# MCU025A_XDS110_USB_Power.net
KiCad netlist of a schematic drawn in Altium Designer
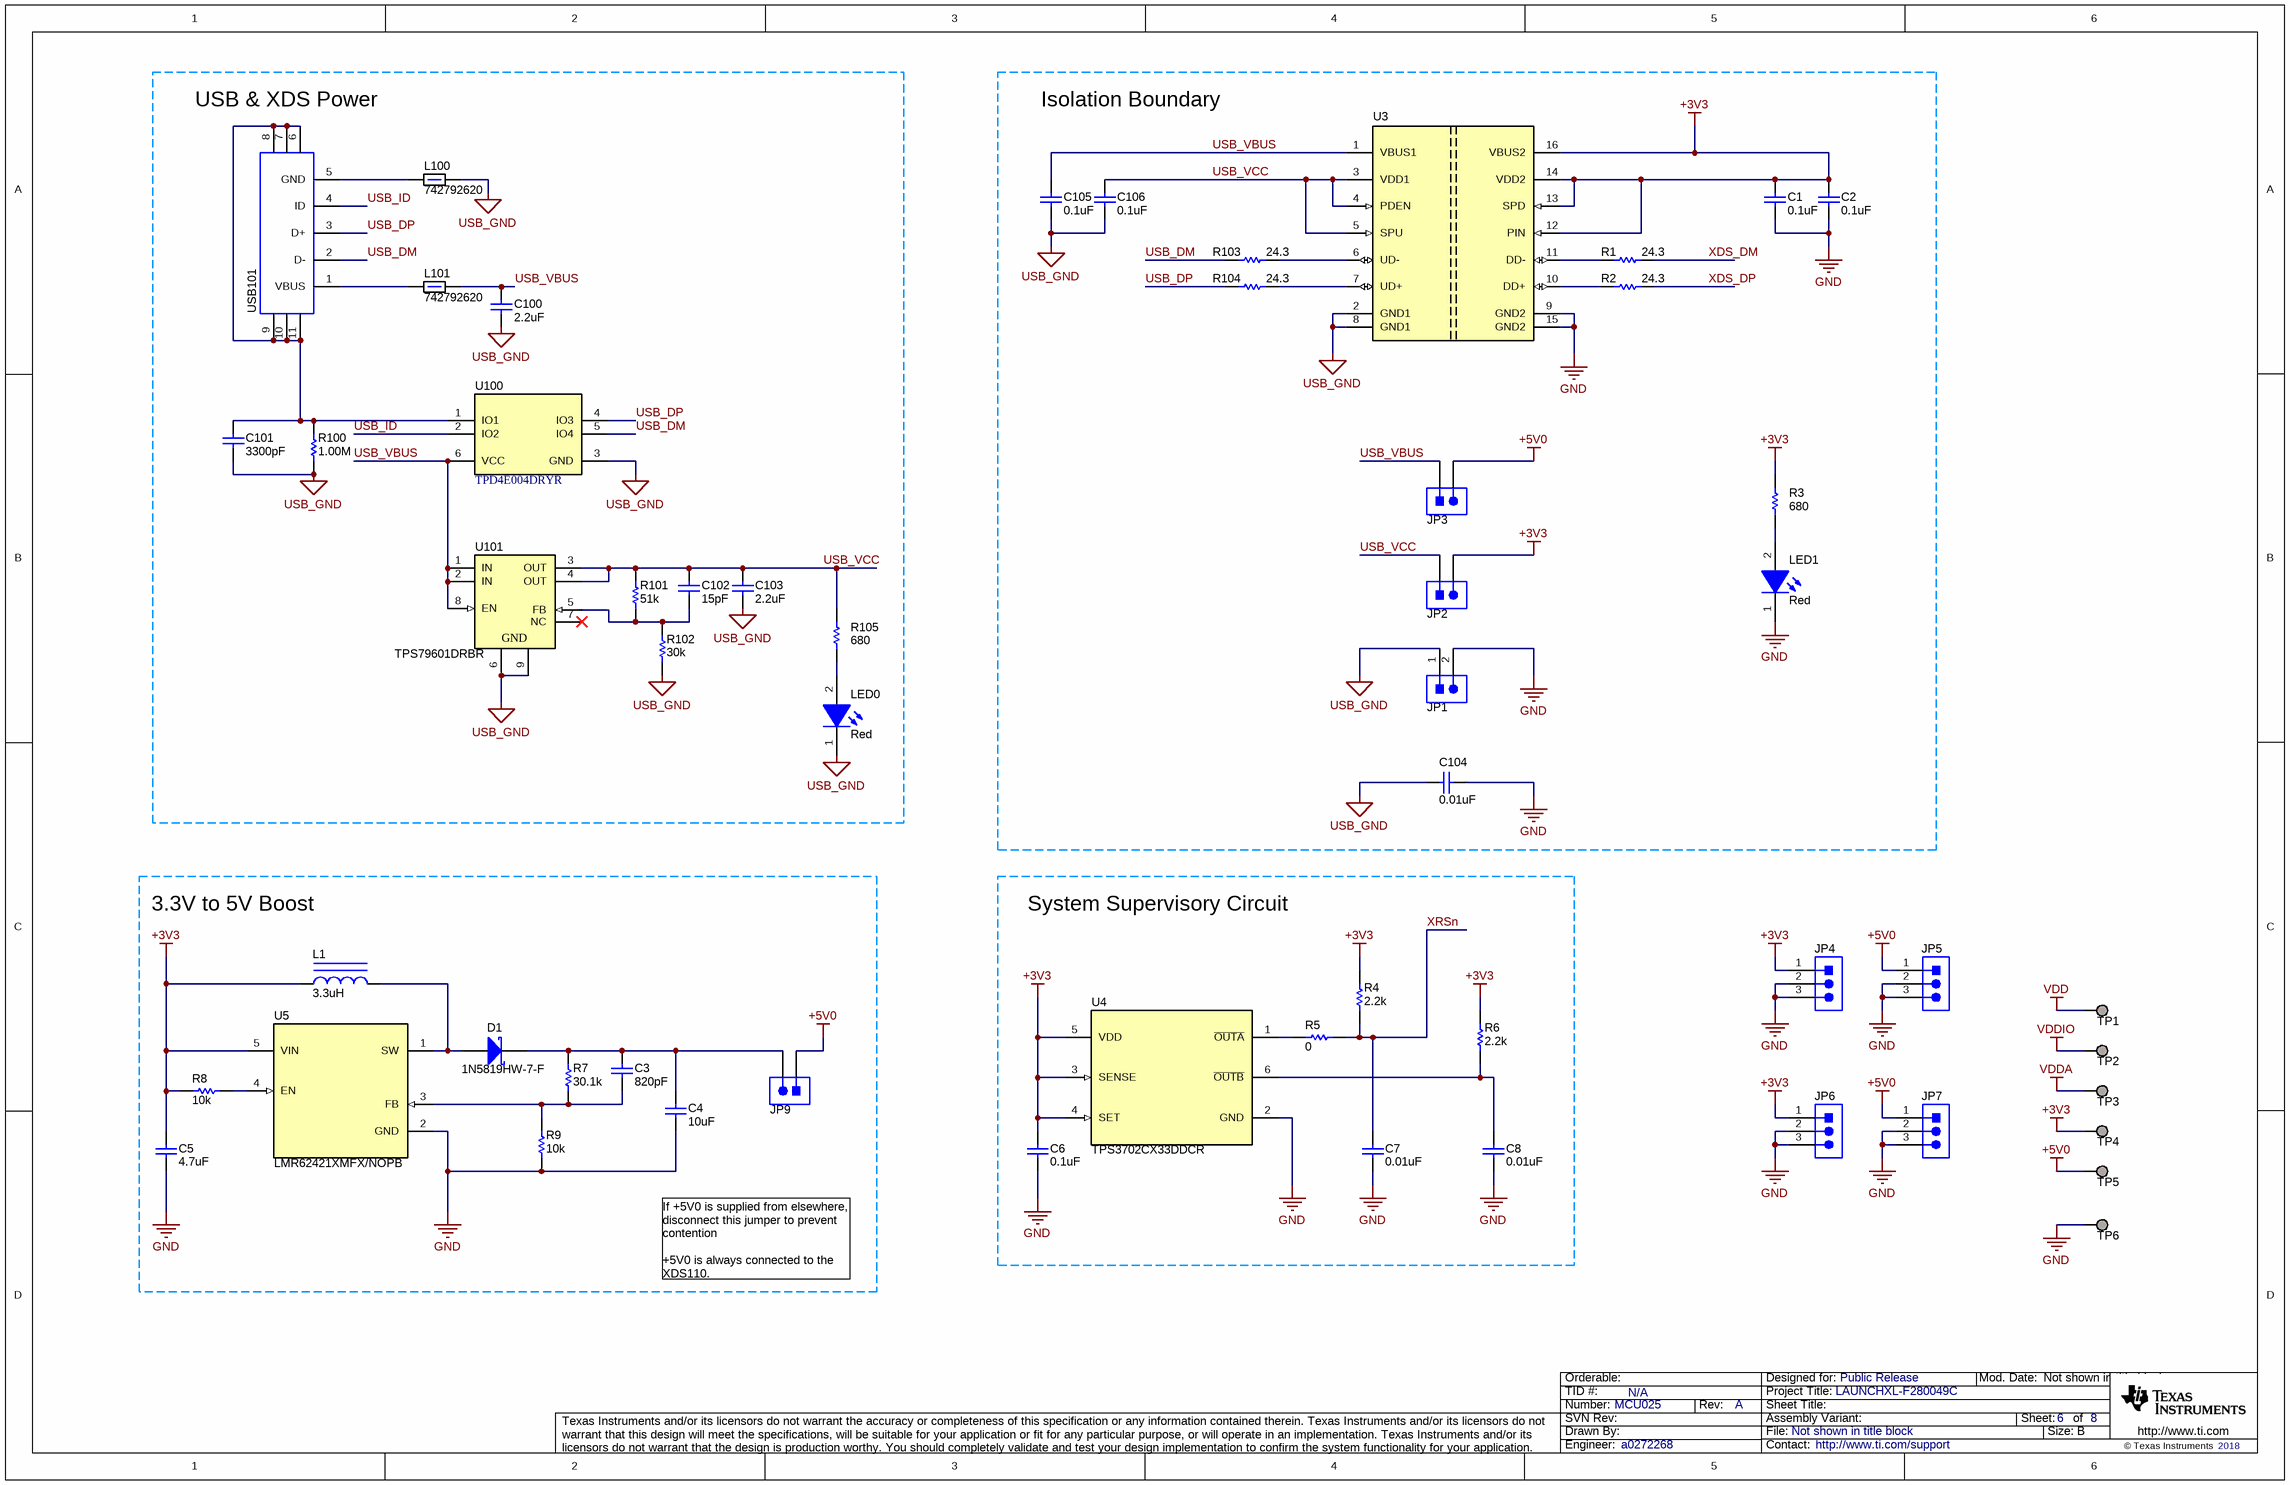
[diagram p0: MCU025A_XDS110_USB_Power.SchDoc]

(export (version "E")
  (design (tool "Eeschema 10.0.6"))
  (components
    (comp (ref "C1")
      (value "GRM155R71A104KA01D")
      (footprint "0402")
      (description "CAP, CERM, 0.1 uF, 10 V, +/- 10%, X7R, 0402")
      (fields
        (field (name "VALUEDISPLAYED") "0.1uF")
        (field (name "MANUFACTURER") "MuRata")
        (field (name "PUBLISHER") "Texas Instruments")
      )
      (libsource (lib "Altium Vault - TI") (part "Capacitor"))
    )
    (comp (ref "C2")
      (value "GRM155R71A104KA01D")
      (footprint "0402")
      (description "CAP, CERM, 0.1 uF, 10 V, +/- 10%, X7R, 0402")
      (fields
        (field (name "VALUEDISPLAYED") "0.1uF")
        (field (name "MANUFACTURER") "MuRata")
        (field (name "PUBLISHER") "Texas Instruments")
      )
      (libsource (lib "Altium Vault - TI") (part "Capacitor"))
    )
    (comp (ref "C3")
      (value "GRM1555C1H821JA01D")
      (footprint "0402")
      (description "CAP, CERM, 820 pF, 50 V, +/- 5%, C0G/NP0, 0402")
      (fields
        (field (name "VALUEDISPLAYED") "820pF")
        (field (name "MANUFACTURER") "MuRata")
        (field (name "PUBLISHER") "Texas Instruments")
      )
      (libsource (lib "Altium Vault - TI") (part "Capacitor"))
    )
    (comp (ref "C4")
      (value "GRM32DR71E106KA12L")
      (footprint "1210_220")
      (description "CAP, CERM, 10 uF, 25 V, +/- 10%, X7R, 1210")
      (fields
        (field (name "VALUEDISPLAYED") "10uF")
        (field (name "MANUFACTURER") "MuRata")
        (field (name "PUBLISHER") "Texas Instruments")
      )
      (libsource (lib "Altium Vault - TI") (part "Capacitor"))
    )
    (comp (ref "C5")
      (value "GRM155R60J475ME47D")
      (footprint "0402")
      (description "CAP, CERM, 4.7 uF, 6.3 V, +/- 20%, X5R, 0402")
      (fields
        (field (name "VALUEDISPLAYED") "4.7uF")
        (field (name "MANUFACTURER") "MuRata")
        (field (name "PUBLISHER") "Texas Instruments")
      )
      (libsource (lib "Altium Vault - TI") (part "Capacitor"))
    )
    (comp (ref "C6")
      (value "GRM155R71A104KA01D")
      (footprint "0402")
      (description "CAP, CERM, 0.1 uF, 10 V, +/- 10%, X7R, 0402")
      (fields
        (field (name "VALUEDISPLAYED") "0.1uF")
        (field (name "MANUFACTURER") "MuRata")
        (field (name "PUBLISHER") "Texas Instruments")
      )
      (libsource (lib "Altium Vault - TI") (part "Capacitor"))
    )
    (comp (ref "C7")
      (value "GRM155R71E103KA01D")
      (footprint "0402")
      (description "CAP, CERM, 0.01 uF, 25 V, +/- 10%, X7R, 0402")
      (fields
        (field (name "VALUEDISPLAYED") "0.01uF")
        (field (name "MANUFACTURER") "MuRata")
        (field (name "PUBLISHER") "Texas Instruments")
      )
      (libsource (lib "Altium Vault - TI") (part "Capacitor"))
    )
    (comp (ref "C8")
      (value "GRM155R71E103KA01D")
      (footprint "0402")
      (description "CAP, CERM, 0.01 uF, 25 V, +/- 10%, X7R, 0402")
      (fields
        (field (name "VALUEDISPLAYED") "0.01uF")
        (field (name "MANUFACTURER") "MuRata")
        (field (name "PUBLISHER") "Texas Instruments")
      )
      (libsource (lib "Altium Vault - TI") (part "Capacitor"))
    )
    (comp (ref "C100")
      (value "GRM155R60J225KE95D")
      (footprint "0402")
      (description "CAP, CERM, 2.2 uF, 6.3 V, +/- 10%, X5R, 0402")
      (fields
        (field (name "VALUEDISPLAYED") "2.2uF")
        (field (name "MANUFACTURER") "MuRata")
        (field (name "PUBLISHER") "Texas Instruments")
      )
      (libsource (lib "Altium Vault - TI") (part "Capacitor"))
    )
    (comp (ref "C101")
      (value "GRM155R71H332KA01D")
      (footprint "0402")
      (description "CAP, CERM, 3300 pF, 50 V, +/- 10%, X7R, 0402")
      (fields
        (field (name "VALUEDISPLAYED") "3300pF")
        (field (name "MANUFACTURER") "MuRata")
        (field (name "PUBLISHER") "Texas Instruments")
      )
      (libsource (lib "Altium Vault - TI") (part "Capacitor"))
    )
    (comp (ref "C102")
      (value "GRM1555C1H150JA01D")
      (footprint "0402")
      (description "CAP, CERM, 15 pF, 50 V, +/- 5%, C0G/NP0, 0402")
      (fields
        (field (name "VALUEDISPLAYED") "15pF")
        (field (name "MANUFACTURER") "MuRata")
        (field (name "PUBLISHER") "Texas Instruments")
      )
      (libsource (lib "Altium Vault - TI") (part "Capacitor"))
    )
    (comp (ref "C103")
      (value "GRM155R60J225KE95D")
      (footprint "0402")
      (description "CAP, CERM, 2.2 uF, 6.3 V, +/- 10%, X5R, 0402")
      (fields
        (field (name "VALUEDISPLAYED") "2.2uF")
        (field (name "MANUFACTURER") "MuRata")
        (field (name "PUBLISHER") "Texas Instruments")
      )
      (libsource (lib "Altium Vault - TI") (part "Capacitor"))
    )
    (comp (ref "C104")
      (value "1812SC103KAT1A")
      (footprint "1812")
      (description "CAP, CERM, 0.01 uF, 1500 V, +/- 10%, X7R, 1812")
      (fields
        (field (name "VALUEDISPLAYED") "0.01uF")
        (field (name "MANUFACTURER") "AVX")
        (field (name "PUBLISHER") "Texas Instruments")
      )
      (libsource (lib "Altium Vault - TI") (part "Capacitor"))
    )
    (comp (ref "C105")
      (value "GRM155R71A104KA01D")
      (footprint "0402")
      (description "CAP, CERM, 0.1 uF, 10 V, +/- 10%, X7R, 0402")
      (fields
        (field (name "VALUEDISPLAYED") "0.1uF")
        (field (name "MANUFACTURER") "MuRata")
        (field (name "PUBLISHER") "Texas Instruments")
      )
      (libsource (lib "Altium Vault - TI") (part "Capacitor"))
    )
    (comp (ref "C106")
      (value "GRM155R71A104KA01D")
      (footprint "0402")
      (description "CAP, CERM, 0.1 uF, 10 V, +/- 10%, X7R, 0402")
      (fields
        (field (name "VALUEDISPLAYED") "0.1uF")
        (field (name "MANUFACTURER") "MuRata")
        (field (name "PUBLISHER") "Texas Instruments")
      )
      (libsource (lib "Altium Vault - TI") (part "Capacitor"))
    )
    (comp (ref "D1")
      (value "1N5819HW-7-F")
      (footprint "SOD-123")
      (description "Diode, Schottky, 40 V, 1 A, SOD-123")
      (fields (field (name "MANUFACTURER") "Diodes Inc.") (field (name "PUBLISHER") "Texas Instruments"))
      (libsource (lib "Altium Vault - TI") (part "DIODE_SCHOTTKY"))
    )
    (comp (ref "JP1")
      (value "61300211121")
      (footprint "WURTH_61300211121")
      (description "Header, 2.54 mm, 2x1, Gold, TH")
      (fields (field (name "MANUFACTURER") "Wurth Elektronik") (field (name "PUBLISHER") "Texas Instruments"))
      (libsource (lib "Altium Vault - TI") (part "Header_2x1"))
    )
    (comp (ref "JP2")
      (value "61300211121")
      (footprint "WURTH_61300211121")
      (description "Header, 2.54 mm, 2x1, Gold, TH")
      (fields (field (name "MANUFACTURER") "Wurth Elektronik") (field (name "PUBLISHER") "Texas Instruments"))
      (libsource (lib "") (part "CMP-0054794-1_1"))
    )
    (comp (ref "JP3")
      (value "61300211121")
      (footprint "WURTH_61300211121")
      (description "Header, 2.54 mm, 2x1, Gold, TH")
      (fields (field (name "MANUFACTURER") "Wurth Elektronik") (field (name "PUBLISHER") "Texas Instruments"))
      (libsource (lib "") (part "CMP-0054794-1_1"))
    )
    (comp (ref "JP4")
      (value "61300311121")
      (footprint "WURTH_61300311121")
      (description "Header, 2.54 mm, 3x1, Gold, TH")
      (fields (field (name "MANUFACTURER") "Wurth Elektronik") (field (name "PUBLISHER") "Texas Instruments"))
      (libsource (lib "Altium Vault - TI") (part "Header_3x1"))
    )
    (comp (ref "JP5")
      (value "61300311121")
      (footprint "WURTH_61300311121")
      (description "Header, 2.54 mm, 3x1, Gold, TH")
      (fields (field (name "MANUFACTURER") "Wurth Elektronik") (field (name "PUBLISHER") "Texas Instruments"))
      (libsource (lib "Altium Vault - TI") (part "Header_3x1"))
    )
    (comp (ref "JP6")
      (value "61300311121")
      (footprint "WURTH_61300311121")
      (description "Header, 2.54 mm, 3x1, Gold, TH")
      (fields (field (name "MANUFACTURER") "Wurth Elektronik") (field (name "PUBLISHER") "Texas Instruments"))
      (libsource (lib "Altium Vault - TI") (part "Header_3x1"))
    )
    (comp (ref "JP7")
      (value "61300311121")
      (footprint "WURTH_61300311121")
      (description "Header, 2.54 mm, 3x1, Gold, TH")
      (fields (field (name "MANUFACTURER") "Wurth Elektronik") (field (name "PUBLISHER") "Texas Instruments"))
      (libsource (lib "Altium Vault - TI") (part "Header_3x1"))
    )
    (comp (ref "JP9")
      (value "61300211121")
      (footprint "WURTH_61300211121")
      (description "Header, 2.54 mm, 2x1, Gold, TH")
      (fields (field (name "MANUFACTURER") "Wurth Elektronik") (field (name "PUBLISHER") "Texas Instruments"))
      (libsource (lib "Altium Vault - TI") (part "CMP-0054794-1"))
    )
    (comp (ref "L1")
      (value "744025003")
      (footprint "WE-TPC_2828")
      (description "Inductor, Shielded Drum Core, Ferrite, 3.3 uH, 1.5 A, 0.085 ohm, SMD")
      (fields
        (field (name "VALUEDISPLAYED") "3.3uH")
        (field (name "MANUFACTURER") "Wurth Elektronik")
        (field (name "PUBLISHER") "Texas Instruments")
      )
      (libsource (lib "Altium Vault - TI") (part "Inductor_Iron"))
    )
    (comp (ref "L100")
      (value "742792620")
      (footprint "0603")
      (description "Ferrite Bead, 100 ohm @ 100 MHz, 0.5 A, 0603")
      (fields (field (name "MANUFACTURER") "Wurth Elektronik") (field (name "PUBLISHER") "Texas Instruments"))
      (libsource (lib "Altium Vault - TI") (part "Ferrite_Bead"))
    )
    (comp (ref "L101")
      (value "742792620")
      (footprint "0603")
      (description "Ferrite Bead, 100 ohm @ 100 MHz, 0.5 A, 0603")
      (fields (field (name "MANUFACTURER") "Wurth Elektronik") (field (name "PUBLISHER") "Texas Instruments"))
      (libsource (lib "Altium Vault - TI") (part "Ferrite_Bead"))
    )
    (comp (ref "LED0")
      (value "Red")
      (footprint "WL-SMCW_RED_0805")
      (description "LED, Red, SMD")
      (fields
        (field (name "MANUFACTURER") "Wurth Elektronik")
        (field (name "PARTNUMBER") "150080SS75000")
        (field (name "PUBLISHER") "Texas Instruments")
      )
      (libsource (lib "Altium Vault - TI") (part "LED_A2_K1"))
    )
    (comp (ref "LED1")
      (value "Red")
      (footprint "WL-SMCW_RED_0805")
      (description "LED, Red, SMD")
      (fields
        (field (name "MANUFACTURER") "Wurth Elektronik")
        (field (name "PARTNUMBER") "150080SS75000")
        (field (name "PUBLISHER") "Texas Instruments")
      )
      (libsource (lib "Altium Vault - TI") (part "LED_A2_K1"))
    )
    (comp (ref "R1")
      (value "CRCW040224R3FKED")
      (footprint "0402")
      (description "RES, 24.3, 1%, 0.063 W, AEC-Q200 Grade 0, 0402")
      (fields (field (name "VALUEDISPLAYED") "24.3") (field (name "MANUFACTURER") "Vishay-Dale"))
      (libsource (lib "Altium Vault - TI") (part "Resistor"))
    )
    (comp (ref "R2")
      (value "CRCW040224R3FKED")
      (footprint "0402")
      (description "RES, 24.3, 1%, 0.063 W, AEC-Q200 Grade 0, 0402")
      (fields (field (name "VALUEDISPLAYED") "24.3") (field (name "MANUFACTURER") "Vishay-Dale"))
      (libsource (lib "Altium Vault - TI") (part "Resistor"))
    )
    (comp (ref "R3")
      (value "CRCW0402680RJNED")
      (footprint "0402")
      (description "RES, 680, 5%, 0.063 W, AEC-Q200 Grade 0, 0402")
      (fields (field (name "MANUFACTURER") "Vishay-Dale") (field (name "VALUEDISPLAYED") "680"))
      (libsource (lib "Altium Vault - TI") (part "CMP-0026962-3"))
    )
    (comp (ref "R4")
      (value "CRCW04022K20JNED")
      (footprint "0402")
      (description "RES, 2.2 k, 5%, 0.063 W, AEC-Q200 Grade 0, 0402")
      (fields (field (name "VALUEDISPLAYED") "2.2k") (field (name "MANUFACTURER") "Vishay-Dale"))
      (libsource (lib "Altium Vault - TI") (part "Resistor"))
    )
    (comp (ref "R5")
      (value "CRCW04020000Z0ED")
      (footprint "0402")
      (description "RES, 0, 5%, 0.063 W, AEC-Q200 Grade 0, 0402")
      (fields (field (name "VALUEDISPLAYED") "0") (field (name "MANUFACTURER") "Vishay-Dale"))
      (libsource (lib "Altium Vault - TI") (part "Resistor"))
    )
    (comp (ref "R6")
      (value "CRCW06032K20JNEA")
      (footprint "0603")
      (description "RES, 2.2 k, 5%, 0.1 W, AEC-Q200 Grade 0, 0603")
      (fields (field (name "VALUEDISPLAYED") "2.2k") (field (name "MANUFACTURER") "Vishay-Dale"))
      (libsource (lib "Altium Vault - TI") (part "Resistor"))
    )
    (comp (ref "R7")
      (value "RC0402FR-0730K1L")
      (footprint "0402")
      (description "RES, 30.1 k, 1%, 0.063 W, 0402")
      (fields
        (field (name "VALUEDISPLAYED") "30.1k")
        (field (name "MANUFACTURER") "Yageo America")
        (field (name "PUBLISHER") "Texas Instruments")
      )
      (libsource (lib "Altium Vault - TI") (part "Resistor"))
    )
    (comp (ref "R8")
      (value "CRCW040210K0JNED")
      (footprint "0402")
      (description "RES, 10 k, 5%, 0.063 W, AEC-Q200 Grade 0, 0402")
      (fields (field (name "VALUEDISPLAYED") "10k") (field (name "MANUFACTURER") "Vishay-Dale"))
      (libsource (lib "Altium Vault - TI") (part "Resistor"))
    )
    (comp (ref "R9")
      (value "CRCW040210K0JNED")
      (footprint "0402")
      (description "RES, 10 k, 5%, 0.063 W, AEC-Q200 Grade 0, 0402")
      (fields (field (name "VALUEDISPLAYED") "10k") (field (name "MANUFACTURER") "Vishay-Dale"))
      (libsource (lib "Altium Vault - TI") (part "Resistor"))
    )
    (comp (ref "R100")
      (value "CRCW04021M00FKED")
      (footprint "0402")
      (description "RES, 1.00 M, 1%, 0.063 W, AEC-Q200 Grade 0, 0402")
      (fields (field (name "VALUEDISPLAYED") "1.00M") (field (name "MANUFACTURER") "Vishay-Dale"))
      (libsource (lib "Altium Vault - TI") (part "Resistor"))
    )
    (comp (ref "R101")
      (value "CRCW040251K0JNED")
      (footprint "0402")
      (description "RES, 51 k, 5%, 0.063 W, AEC-Q200 Grade 0, 0402")
      (fields (field (name "VALUEDISPLAYED") "51k") (field (name "MANUFACTURER") "Vishay-Dale"))
      (libsource (lib "Altium Vault - TI") (part "Resistor"))
    )
    (comp (ref "R102")
      (value "CRCW040230K0JNED")
      (footprint "0402")
      (description "RES, 30 k, 5%, 0.063 W, AEC-Q200 Grade 0, 0402")
      (fields (field (name "VALUEDISPLAYED") "30k") (field (name "MANUFACTURER") "Vishay-Dale"))
      (libsource (lib "Altium Vault - TI") (part "Resistor"))
    )
    (comp (ref "R103")
      (value "CRCW040224R3FKED")
      (footprint "0402")
      (description "RES, 24.3, 1%, 0.063 W, AEC-Q200 Grade 0, 0402")
      (fields (field (name "VALUEDISPLAYED") "24.3") (field (name "MANUFACTURER") "Vishay-Dale"))
      (libsource (lib "Altium Vault - TI") (part "Resistor"))
    )
    (comp (ref "R104")
      (value "CRCW040224R3FKED")
      (footprint "0402")
      (description "RES, 24.3, 1%, 0.063 W, AEC-Q200 Grade 0, 0402")
      (fields (field (name "VALUEDISPLAYED") "24.3") (field (name "MANUFACTURER") "Vishay-Dale"))
      (libsource (lib "Altium Vault - TI") (part "Resistor"))
    )
    (comp (ref "R105")
      (value "CRCW0402680RJNED")
      (footprint "0402")
      (description "RES, 680, 5%, 0.063 W, AEC-Q200 Grade 0, 0402")
      (fields (field (name "MANUFACTURER") "Vishay-Dale") (field (name "VALUEDISPLAYED") "680"))
      (libsource (lib "Altium Vault - TI") (part "CMP-0026962-3"))
    )
    (comp (ref "TP1")
      (value "TESTPOINT")
      (footprint "TESTPOINT")
      (description "TEST POINT.  No entry in BOM.")
      (libsource (lib "Altium Vault - TI") (part "TESTPOINT"))
    )
    (comp (ref "TP2")
      (value "TESTPOINT")
      (footprint "TESTPOINT")
      (description "TEST POINT.  No entry in BOM.")
      (libsource (lib "Altium Vault - TI") (part "TESTPOINT"))
    )
    (comp (ref "TP3")
      (value "TESTPOINT")
      (footprint "TESTPOINT")
      (description "TEST POINT.  No entry in BOM.")
      (libsource (lib "Altium Vault - TI") (part "TESTPOINT"))
    )
    (comp (ref "TP4")
      (value "TESTPOINT")
      (footprint "TESTPOINT")
      (description "TEST POINT.  No entry in BOM.")
      (libsource (lib "Altium Vault - TI") (part "TESTPOINT"))
    )
    (comp (ref "TP5")
      (value "TESTPOINT")
      (footprint "TESTPOINT")
      (description "TEST POINT.  No entry in BOM.")
      (libsource (lib "Altium Vault - TI") (part "TESTPOINT"))
    )
    (comp (ref "TP6")
      (value "TESTPOINT")
      (footprint "TESTPOINT")
      (description "TEST POINT.  No entry in BOM.")
      (libsource (lib "Altium Vault - TI") (part "TESTPOINT"))
    )
    (comp (ref "U3")
      (value "ADuM3160BRWZ")
      (footprint "SOIC-16")
      (description "Full/Low Speed 2.5 kV USB Digital Isolator, SOIC-16")
      (fields (field (name "MANUFACTURER") "Analog Devices") (field (name "PUBLISHER") "Texas Instruments"))
      (libsource (lib "Altium Vault - TI") (part "ADuM3160"))
    )
    (comp (ref "U4")
      (value "TPS3702CX33DDCR")
      (footprint "DDC0006A_N")
      (description "High-Accuracy, Fixed-Threshold OV/UV Monitor, DDC0006A (SOT-23-T-6)")
      (fields
        (field (name "ALTERNATE PARTNUMBER") "TPS3702CX33DDCT")
        (field (name "MANUFACTURER") "Texas Instruments")
        (field (name "PUBLISHER") "Texas Instruments")
      )
      (libsource (lib "Altium Vault - TI") (part "TPS3702"))
    )
    (comp (ref "U5")
      (value "LMR62421XMFX/NOPB")
      (footprint "DBV0005A_N")
      (description "SIMPLE SWITCHER 2.7V to 5.5V, 2.1A Step-Up Regulator in SOT-23, DBV0005A (SOT-23-5)")
      (fields
        (field (name "ALTERNATE PARTNUMBER") "LMR62421XMFE/NOPB")
        (field (name "MANUFACTURER") "Texas Instruments")
        (field (name "PUBLISHER") "Texas Instruments")
      )
      (libsource (lib "Altium Vault - TI") (part "LMR62421DBV"))
    )
    (comp (ref "U100")
      (value "TPD4E004DRYR")
      (footprint "DRY0006A")
      (fields (field (name "MANUFACTURER") "Texas Instruments"))
      (libsource (lib "Altium Vault - TI") (part "TI-TPD4E004-SON_DRY-6"))
    )
    (comp (ref "U101")
      (value "TPS79601DRBR")
      (footprint "DRB0008B")
      (fields (field (name "MANUFACTURER") "Texas Instruments"))
      (libsource (lib "Altium Vault - TI") (part "CMP-0036402-3"))
    )
    (comp (ref "USB101")
      (value "1051640001")
      (footprint "Molex_1051640001")
      (description "Receptacle, USB 2.0, Micro B, 5 Position, R/A, SMT")
      (fields (field (name "MANUFACTURER") "Molex") (field (name "PUBLISHER") "Texas Instruments"))
      (libsource (lib "Altium Vault - TI") (part "CONN_USB_MicroMini_6Shld"))
    )
  )
  (nets
    (net (code "1") (name "+3V3") (class "Default")
      (node (ref "C1") (pin "2") (pinfunction "2_2") (pintype "passive"))
      (node (ref "C2") (pin "2") (pinfunction "2_2") (pintype "passive"))
      (node (ref "C5") (pin "1") (pinfunction "1_1") (pintype "passive"))
      (node (ref "C6") (pin "2") (pinfunction "2_2") (pintype "passive"))
      (node (ref "JP2") (pin "2") (pinfunction "2_2") (pintype "passive"))
      (node (ref "JP4") (pin "1") (pinfunction "1_1") (pintype "passive"))
      (node (ref "JP6") (pin "1") (pinfunction "1_1") (pintype "passive"))
      (node (ref "L1") (pin "1") (pinfunction "1_1") (pintype "passive"))
      (node (ref "R3") (pin "2") (pinfunction "2_2") (pintype "passive"))
      (node (ref "R4") (pin "2") (pinfunction "2_2") (pintype "passive"))
      (node (ref "R6") (pin "2") (pinfunction "2_2") (pintype "passive"))
      (node (ref "R8") (pin "2") (pinfunction "2_2") (pintype "passive"))
      (node (ref "TP4") (pin "1") (pintype "passive"))
      (node (ref "U3") (pin "12") (pinfunction "PIN_12") (pintype "input"))
      (node (ref "U3") (pin "13") (pinfunction "SPD_13") (pintype "input"))
      (node (ref "U3") (pin "14") (pinfunction "VDD2_14") (pintype "power_in"))
      (node (ref "U3") (pin "16") (pinfunction "VBUS2_16") (pintype "power_in"))
      (node (ref "U4") (pin "3") (pinfunction "SENSE_3") (pintype "input"))
      (node (ref "U4") (pin "4") (pinfunction "SET_4") (pintype "input"))
      (node (ref "U4") (pin "5") (pinfunction "VDD_5") (pintype "power_in"))
      (node (ref "U5") (pin "5") (pinfunction "VIN_5") (pintype "power_in"))
    )
    (net (code "2") (name "+5V0") (class "Default")
      (node (ref "JP3") (pin "2") (pinfunction "2_2") (pintype "passive"))
      (node (ref "JP5") (pin "1") (pinfunction "1_1") (pintype "passive"))
      (node (ref "JP7") (pin "1") (pinfunction "1_1") (pintype "passive"))
      (node (ref "JP9") (pin "1") (pinfunction "1_1") (pintype "passive"))
      (node (ref "TP5") (pin "1") (pintype "passive"))
    )
    (net (code "3") (name "/USB_DM") (class "Default")
      (node (ref "R103") (pin "1") (pinfunction "1_1") (pintype "passive"))
      (node (ref "U100") (pin "5") (pinfunction "IO4_5") (pintype "passive"))
      (node (ref "USB101") (pin "2") (pinfunction "D-_2") (pintype "passive"))
    )
    (net (code "4") (name "/USB_DP") (class "Default")
      (node (ref "R104") (pin "1") (pinfunction "1_1") (pintype "passive"))
      (node (ref "U100") (pin "4") (pinfunction "IO3_4") (pintype "passive"))
      (node (ref "USB101") (pin "3") (pinfunction "D+_3") (pintype "passive"))
    )
    (net (code "5") (name "/USB_ID") (class "Default")
      (node (ref "U100") (pin "2") (pinfunction "IO2_2") (pintype "passive"))
      (node (ref "USB101") (pin "4") (pinfunction "ID_4") (pintype "passive"))
    )
    (net (code "6") (name "/USB_VBUS") (class "Default")
      (node (ref "C100") (pin "1") (pinfunction "1_1") (pintype "passive"))
      (node (ref "C105") (pin "2") (pinfunction "2_2") (pintype "passive"))
      (node (ref "JP3") (pin "1") (pinfunction "1_1") (pintype "passive"))
      (node (ref "L101") (pin "2") (pinfunction "2_2") (pintype "passive"))
      (node (ref "U100") (pin "6") (pinfunction "VCC_6") (pintype "power_in"))
      (node (ref "U101") (pin "1") (pinfunction "IN_1") (pintype "power_in"))
      (node (ref "U101") (pin "2") (pinfunction "IN_2") (pintype "power_in"))
      (node (ref "U101") (pin "8") (pinfunction "EN_8") (pintype "input"))
      (node (ref "U3") (pin "1") (pinfunction "VBUS1_1") (pintype "power_in"))
    )
    (net (code "7") (name "/USB_VCC") (class "Default")
      (node (ref "C102") (pin "1") (pinfunction "1_1") (pintype "passive"))
      (node (ref "C103") (pin "1") (pinfunction "1_1") (pintype "passive"))
      (node (ref "C106") (pin "2") (pinfunction "2_2") (pintype "passive"))
      (node (ref "JP2") (pin "1") (pinfunction "1_1") (pintype "passive"))
      (node (ref "R101") (pin "2") (pinfunction "2_2") (pintype "passive"))
      (node (ref "R105") (pin "2") (pinfunction "2_2") (pintype "passive"))
      (node (ref "U101") (pin "3") (pinfunction "OUT_3") (pintype "power_in"))
      (node (ref "U101") (pin "4") (pinfunction "OUT_4") (pintype "power_in"))
      (node (ref "U3") (pin "3") (pinfunction "VDD1_3") (pintype "power_in"))
      (node (ref "U3") (pin "4") (pinfunction "PDEN_4") (pintype "input"))
      (node (ref "U3") (pin "5") (pinfunction "SPU_5") (pintype "input"))
    )
    (net (code "8") (name "/XDS_DM") (class "Default")
      (node (ref "R1") (pin "2") (pinfunction "2_2") (pintype "passive"))
    )
    (net (code "9") (name "/XDS_DP") (class "Default")
      (node (ref "R2") (pin "2") (pinfunction "2_2") (pintype "passive"))
    )
    (net (code "10") (name "/XRSn") (class "Default")
      (node (ref "C7") (pin "1") (pinfunction "1_1") (pintype "passive"))
      (node (ref "R4") (pin "1") (pinfunction "1_1") (pintype "passive"))
      (node (ref "R5") (pin "2") (pinfunction "2_2") (pintype "passive"))
    )
    (net (code "11") (name "GND") (class "Default")
      (node (ref "C1") (pin "1") (pinfunction "1_1") (pintype "passive"))
      (node (ref "C104") (pin "1") (pinfunction "1_1") (pintype "passive"))
      (node (ref "C2") (pin "1") (pinfunction "1_1") (pintype "passive"))
      (node (ref "C4") (pin "2") (pinfunction "2_2") (pintype "passive"))
      (node (ref "C5") (pin "2") (pinfunction "2_2") (pintype "passive"))
      (node (ref "C6") (pin "1") (pinfunction "1_1") (pintype "passive"))
      (node (ref "C7") (pin "2") (pinfunction "2_2") (pintype "passive"))
      (node (ref "C8") (pin "2") (pinfunction "2_2") (pintype "passive"))
      (node (ref "JP1") (pin "2") (pinfunction "2_2") (pintype "passive"))
      (node (ref "JP4") (pin "2") (pinfunction "2_2") (pintype "passive"))
      (node (ref "JP4") (pin "3") (pinfunction "3_3") (pintype "passive"))
      (node (ref "JP5") (pin "2") (pinfunction "2_2") (pintype "passive"))
      (node (ref "JP5") (pin "3") (pinfunction "3_3") (pintype "passive"))
      (node (ref "JP6") (pin "2") (pinfunction "2_2") (pintype "passive"))
      (node (ref "JP6") (pin "3") (pinfunction "3_3") (pintype "passive"))
      (node (ref "JP7") (pin "2") (pinfunction "2_2") (pintype "passive"))
      (node (ref "JP7") (pin "3") (pinfunction "3_3") (pintype "passive"))
      (node (ref "LED1") (pin "1") (pinfunction "K_1") (pintype "passive"))
      (node (ref "R9") (pin "1") (pinfunction "1_1") (pintype "passive"))
      (node (ref "TP6") (pin "1") (pintype "passive"))
      (node (ref "U3") (pin "15") (pinfunction "GND2_15") (pintype "power_in"))
      (node (ref "U3") (pin "9") (pinfunction "GND2_9") (pintype "power_in"))
      (node (ref "U4") (pin "2") (pinfunction "GND_2") (pintype "power_in"))
      (node (ref "U5") (pin "2") (pinfunction "GND_2") (pintype "power_in"))
    )
    (net (code "12") (name "Net-(D1-A)") (class "Default")
      (node (ref "D1") (pin "2") (pinfunction "A_2") (pintype "passive"))
      (node (ref "L1") (pin "2") (pinfunction "2_2") (pintype "passive"))
      (node (ref "U5") (pin "1") (pinfunction "SW_1") (pintype "power_in"))
    )
    (net (code "13") (name "Net-(D1-K)") (class "Default")
      (node (ref "C3") (pin "1") (pinfunction "1_1") (pintype "passive"))
      (node (ref "C4") (pin "1") (pinfunction "1_1") (pintype "passive"))
      (node (ref "D1") (pin "1") (pinfunction "K_1") (pintype "passive"))
      (node (ref "JP9") (pin "2") (pinfunction "2_2") (pintype "passive"))
      (node (ref "R7") (pin "2") (pinfunction "2_2") (pintype "passive"))
    )
    (net (code "14") (name "Net-(LED0-A)") (class "Default")
      (node (ref "LED0") (pin "2") (pinfunction "A_2") (pintype "passive"))
      (node (ref "R105") (pin "1") (pinfunction "1_1") (pintype "passive"))
    )
    (net (code "15") (name "Net-(LED1-A)") (class "Default")
      (node (ref "LED1") (pin "2") (pinfunction "A_2") (pintype "passive"))
      (node (ref "R3") (pin "1") (pinfunction "1_1") (pintype "passive"))
    )
    (net (code "16") (name "Net-(U3-DD+)") (class "Default")
      (node (ref "R2") (pin "1") (pinfunction "1_1") (pintype "passive"))
      (node (ref "U3") (pin "10") (pinfunction "DD+_10") (pintype "bidirectional"))
    )
    (net (code "17") (name "Net-(U3-DD-)") (class "Default")
      (node (ref "R1") (pin "1") (pinfunction "1_1") (pintype "passive"))
      (node (ref "U3") (pin "11") (pinfunction "DD-_11") (pintype "bidirectional"))
    )
    (net (code "18") (name "Net-(U3-UD+)") (class "Default")
      (node (ref "R104") (pin "2") (pinfunction "2_2") (pintype "passive"))
      (node (ref "U3") (pin "7") (pinfunction "UD+_7") (pintype "bidirectional"))
    )
    (net (code "19") (name "Net-(U3-UD-)") (class "Default")
      (node (ref "R103") (pin "2") (pinfunction "2_2") (pintype "passive"))
      (node (ref "U3") (pin "6") (pinfunction "UD-_6") (pintype "bidirectional"))
    )
    (net (code "20") (name "Net-(U4-OUTA)") (class "Default")
      (node (ref "R5") (pin "1") (pinfunction "1_1") (pintype "passive"))
      (node (ref "U4") (pin "1") (pinfunction "OUTA_1") (pintype "open_collector"))
    )
    (net (code "21") (name "Net-(U4-OUTB)") (class "Default")
      (node (ref "C8") (pin "1") (pinfunction "1_1") (pintype "passive"))
      (node (ref "R6") (pin "1") (pinfunction "1_1") (pintype "passive"))
      (node (ref "U4") (pin "6") (pinfunction "OUTB_6") (pintype "open_collector"))
    )
    (net (code "22") (name "Net-(U5-EN)") (class "Default")
      (node (ref "R8") (pin "1") (pinfunction "1_1") (pintype "passive"))
      (node (ref "U5") (pin "4") (pinfunction "EN_4") (pintype "input"))
    )
    (net (code "23") (name "Net-(U5-FB)") (class "Default")
      (node (ref "C3") (pin "2") (pinfunction "2_2") (pintype "passive"))
      (node (ref "R7") (pin "1") (pinfunction "1_1") (pintype "passive"))
      (node (ref "R9") (pin "2") (pinfunction "2_2") (pintype "passive"))
      (node (ref "U5") (pin "3") (pinfunction "FB_3") (pintype "input"))
    )
    (net (code "24") (name "Net-(U100-IO1)") (class "Default")
      (node (ref "C101") (pin "1") (pinfunction "1_1") (pintype "passive"))
      (node (ref "R100") (pin "2") (pinfunction "2_2") (pintype "passive"))
      (node (ref "U100") (pin "1") (pinfunction "IO1_1") (pintype "passive"))
      (node (ref "USB101") (pin "10") (pinfunction "10_10") (pintype "passive"))
      (node (ref "USB101") (pin "11") (pinfunction "11_11") (pintype "passive"))
      (node (ref "USB101") (pin "6") (pinfunction "6_6") (pintype "passive"))
      (node (ref "USB101") (pin "7") (pinfunction "7_7") (pintype "passive"))
      (node (ref "USB101") (pin "8") (pinfunction "8_8") (pintype "passive"))
      (node (ref "USB101") (pin "9") (pinfunction "9_9") (pintype "passive"))
    )
    (net (code "25") (name "Net-(U101-FB)") (class "Default")
      (node (ref "C102") (pin "2") (pinfunction "2_2") (pintype "passive"))
      (node (ref "R101") (pin "1") (pinfunction "1_1") (pintype "passive"))
      (node (ref "R102") (pin "2") (pinfunction "2_2") (pintype "passive"))
      (node (ref "U101") (pin "5") (pinfunction "FB_5") (pintype "input"))
    )
    (net (code "26") (name "Net-(USB101-GND)") (class "Default")
      (node (ref "L100") (pin "1") (pinfunction "1_1") (pintype "passive"))
      (node (ref "USB101") (pin "5") (pinfunction "GND_5") (pintype "passive"))
    )
    (net (code "27") (name "Net-(USB101-VBUS)") (class "Default")
      (node (ref "L101") (pin "1") (pinfunction "1_1") (pintype "passive"))
      (node (ref "USB101") (pin "1") (pinfunction "VBUS_1") (pintype "passive"))
    )
    (net (code "28") (name "USB_GND") (class "Default")
      (node (ref "C100") (pin "2") (pinfunction "2_2") (pintype "passive"))
      (node (ref "C101") (pin "2") (pinfunction "2_2") (pintype "passive"))
      (node (ref "C103") (pin "2") (pinfunction "2_2") (pintype "passive"))
      (node (ref "C104") (pin "2") (pinfunction "2_2") (pintype "passive"))
      (node (ref "C105") (pin "1") (pinfunction "1_1") (pintype "passive"))
      (node (ref "C106") (pin "1") (pinfunction "1_1") (pintype "passive"))
      (node (ref "JP1") (pin "1") (pinfunction "1_1") (pintype "passive"))
      (node (ref "L100") (pin "2") (pinfunction "2_2") (pintype "passive"))
      (node (ref "LED0") (pin "1") (pinfunction "K_1") (pintype "passive"))
      (node (ref "R100") (pin "1") (pinfunction "1_1") (pintype "passive"))
      (node (ref "R102") (pin "1") (pinfunction "1_1") (pintype "passive"))
      (node (ref "U100") (pin "3") (pinfunction "GND_3") (pintype "power_in"))
      (node (ref "U101") (pin "6") (pinfunction "GND_6") (pintype "power_in"))
      (node (ref "U101") (pin "9") (pinfunction "GND_9") (pintype "power_in"))
      (node (ref "U3") (pin "2") (pinfunction "GND1_2") (pintype "power_in"))
      (node (ref "U3") (pin "8") (pinfunction "GND1_8") (pintype "power_in"))
    )
    (net (code "29") (name "VDD") (class "Default") (node (ref "TP1") (pin "1") (pintype "passive")))
    (net (code "30") (name "VDDA") (class "Default") (node (ref "TP3") (pin "1") (pintype "passive")))
    (net (code "31") (name "VDDIO") (class "Default") (node (ref "TP2") (pin "1") (pintype "passive")))
    (net (code "32") (name "unconnected-(U101-NC-Pad7)") (class "Default")
      (node (ref "U101") (pin "7") (pinfunction "NC_7") (pintype "passive+no_connect"))
    )
  )
)
